# FTDI___USB.net
KiCad netlist of a schematic drawn in Altium Designer
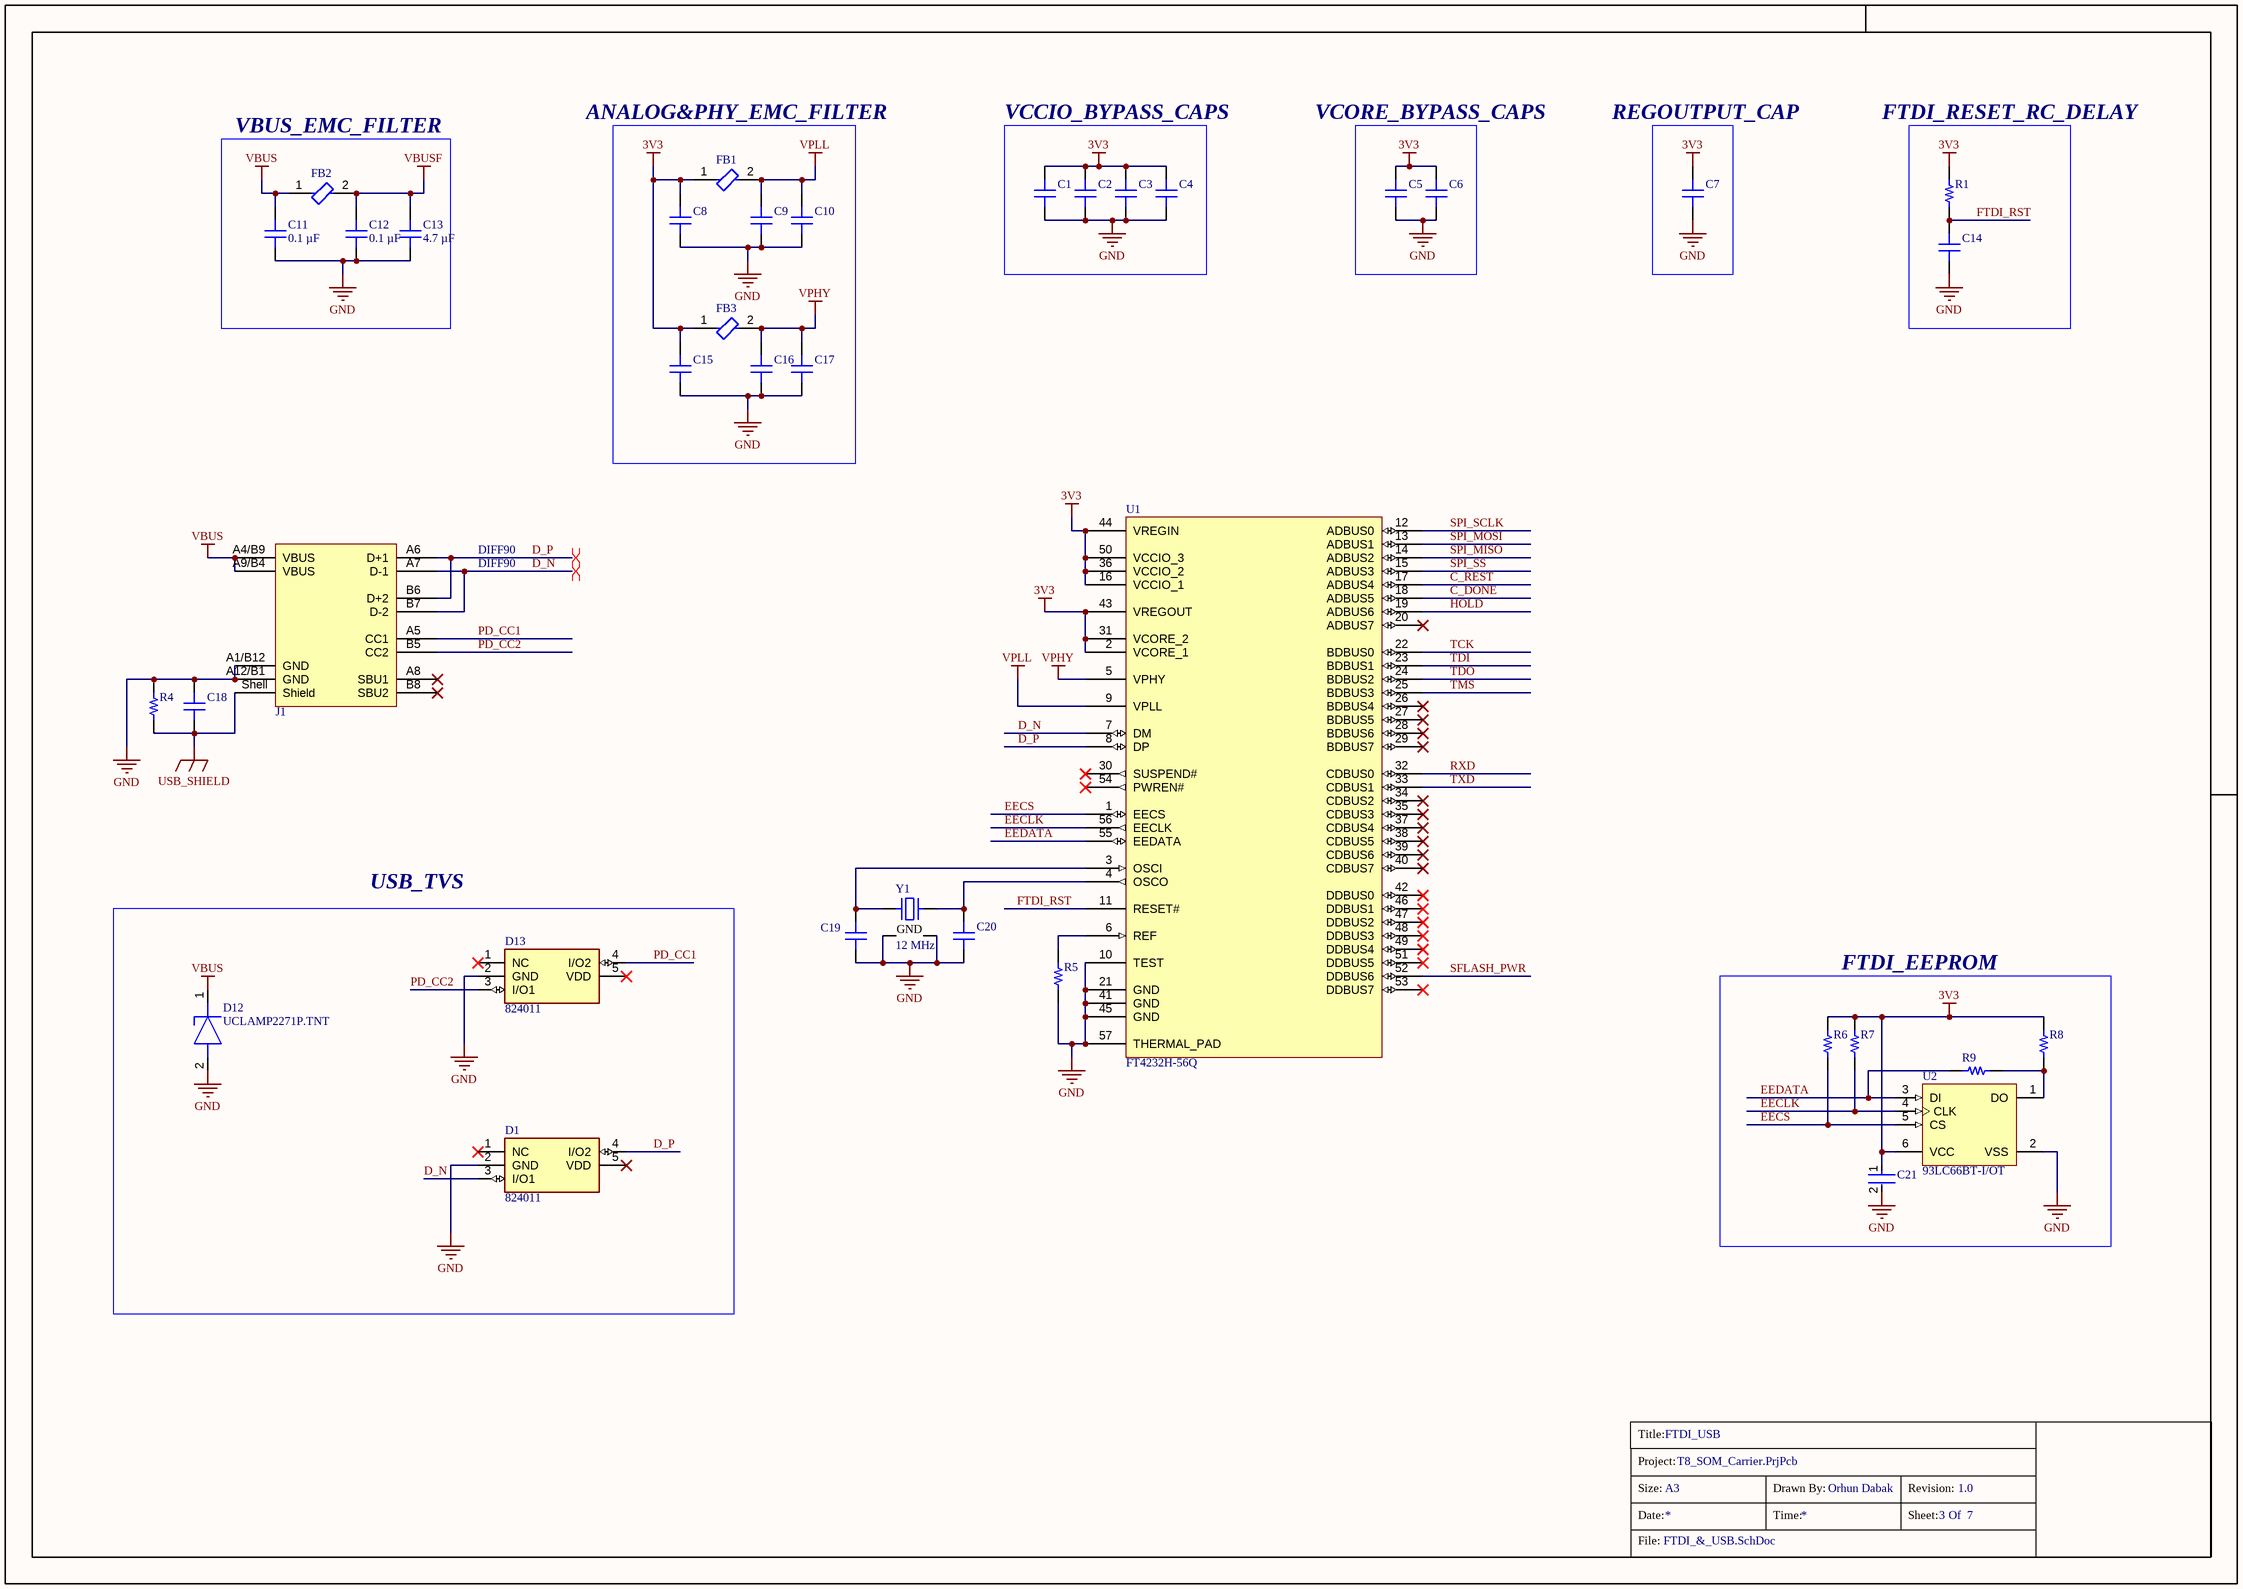
[diagram p0: FTDI_&_USB.SchDoc]

(export (version "E")
  (design (tool "Eeschema 10.0.6"))
  (components
    (comp (ref "C1")
      (value "0.1 µF")
      (footprint "CAP 0402_1005")
      (description "CAP CER 0.1UF 10V X7R 0402")
      (fields (field (name "PART NUMBER") "CC0402KRX7R6BB104") (field (name "MANUFACTURER") "Yageo"))
      (libsource (lib "Celestial Altium Library - altium_library") (part "Capacitor"))
    )
    (comp (ref "C2")
      (value "0.1 µF")
      (footprint "CAP 0402_1005")
      (description "CAP CER 0.1UF 10V X7R 0402")
      (fields (field (name "PART NUMBER") "CC0402KRX7R6BB104") (field (name "MANUFACTURER") "Yageo"))
      (libsource (lib "Celestial Altium Library - altium_library") (part "Capacitor"))
    )
    (comp (ref "C3")
      (value "0.1 µF")
      (footprint "CAP 0402_1005")
      (description "CAP CER 0.1UF 10V X7R 0402")
      (fields (field (name "PART NUMBER") "CC0402KRX7R6BB104") (field (name "MANUFACTURER") "Yageo"))
      (libsource (lib "Celestial Altium Library - altium_library") (part "Capacitor"))
    )
    (comp (ref "C4")
      (value "0.1 µF")
      (footprint "CAP 0402_1005")
      (description "CAP CER 0.1UF 10V X7R 0402")
      (fields (field (name "PART NUMBER") "CC0402KRX7R6BB104") (field (name "MANUFACTURER") "Yageo"))
      (libsource (lib "Celestial Altium Library - altium_library") (part "Capacitor"))
    )
    (comp (ref "C5")
      (value "0.1 µF")
      (footprint "CAP 0402_1005")
      (description "CAP CER 0.1UF 10V X7R 0402")
      (fields (field (name "PART NUMBER") "CC0402KRX7R6BB104") (field (name "MANUFACTURER") "Yageo"))
      (libsource (lib "Celestial Altium Library - altium_library") (part "Capacitor"))
    )
    (comp (ref "C6")
      (value "0.1 µF")
      (footprint "CAP 0402_1005")
      (description "CAP CER 0.1UF 10V X7R 0402")
      (fields (field (name "PART NUMBER") "CC0402KRX7R6BB104") (field (name "MANUFACTURER") "Yageo"))
      (libsource (lib "Celestial Altium Library - altium_library") (part "Capacitor"))
    )
    (comp (ref "C7")
      (value "4.7 µF")
      (footprint "CAP 0402_1005")
      (description "CAP CER 4.7UF 10V X5R 0402")
      (fields
        (field (name "PART NUMBER") "CL05A475MP5NRNC")
        (field (name "MANUFACTURER") "Samsung Electro-Mechanics")
      )
      (libsource (lib "Celestial Altium Library - altium_library") (part "Capacitor"))
    )
    (comp (ref "C8")
      (value "0.1 µF")
      (footprint "CAP 0402_1005")
      (description "CAP CER 0.1UF 10V X7R 0402")
      (fields (field (name "PART NUMBER") "CC0402KRX7R6BB104") (field (name "MANUFACTURER") "Yageo"))
      (libsource (lib "Celestial Altium Library - altium_library") (part "Capacitor"))
    )
    (comp (ref "C9")
      (value "0.1 µF")
      (footprint "CAP 0402_1005")
      (description "CAP CER 0.1UF 10V X7R 0402")
      (fields (field (name "PART NUMBER") "CC0402KRX7R6BB104") (field (name "MANUFACTURER") "Yageo"))
      (libsource (lib "Celestial Altium Library - altium_library") (part "Capacitor"))
    )
    (comp (ref "C10")
      (value "4.7 µF")
      (footprint "CAP 0402_1005")
      (description "CAP CER 4.7UF 10V X5R 0402")
      (fields
        (field (name "PART NUMBER") "CL05A475MP5NRNC")
        (field (name "MANUFACTURER") "Samsung Electro-Mechanics")
      )
      (libsource (lib "Celestial Altium Library - altium_library") (part "Capacitor"))
    )
    (comp (ref "C11")
      (value "0.1 µF")
      (footprint "CAP 0603_1608")
      (description "CAP CER 0.1UF 25V X7R 0603")
      (fields (field (name "PART NUMBER") "C0603X104M3RAC7867") (field (name "MANUFACTURER") "KEMET"))
      (libsource (lib "Celestial Altium Library - altium_library") (part "Capacitor"))
    )
    (comp (ref "C12")
      (value "0.1 µF")
      (footprint "CAP 0603_1608")
      (description "CAP CER 0.1UF 25V X7R 0603")
      (fields (field (name "PART NUMBER") "C0603X104M3RAC7867") (field (name "MANUFACTURER") "KEMET"))
      (libsource (lib "Celestial Altium Library - altium_library") (part "Capacitor"))
    )
    (comp (ref "C13")
      (value "4.7 µF")
      (footprint "CAP 1206_3216 - 0.8MM")
      (description "CAP CER 4.7UF 50V X7R 1206")
      (fields
        (field (name "PART NUMBER") "CL31B475KBHVPNE")
        (field (name "MANUFACTURER") "Samsung Electro-Mechanics")
      )
      (libsource (lib "Celestial Altium Library - altium_library") (part "Capacitor"))
    )
    (comp (ref "C14")
      (value "0.1 µF")
      (footprint "CAP 0402_1005")
      (description "CAP CER 0.1UF 10V X7R 0402")
      (fields (field (name "PART NUMBER") "CC0402KRX7R6BB104") (field (name "MANUFACTURER") "Yageo"))
      (libsource (lib "Celestial Altium Library - altium_library") (part "Capacitor"))
    )
    (comp (ref "C15")
      (value "0.1 µF")
      (footprint "CAP 0402_1005")
      (description "CAP CER 0.1UF 10V X7R 0402")
      (fields (field (name "PART NUMBER") "CC0402KRX7R6BB104") (field (name "MANUFACTURER") "Yageo"))
      (libsource (lib "Celestial Altium Library - altium_library") (part "Capacitor"))
    )
    (comp (ref "C16")
      (value "0.1 µF")
      (footprint "CAP 0402_1005")
      (description "CAP CER 0.1UF 10V X7R 0402")
      (fields (field (name "PART NUMBER") "CC0402KRX7R6BB104") (field (name "MANUFACTURER") "Yageo"))
      (libsource (lib "Celestial Altium Library - altium_library") (part "Capacitor"))
    )
    (comp (ref "C17")
      (value "4.7 µF")
      (footprint "CAP 0402_1005")
      (description "CAP CER 4.7UF 10V X5R 0402")
      (fields
        (field (name "PART NUMBER") "CL05A475MP5NRNC")
        (field (name "MANUFACTURER") "Samsung Electro-Mechanics")
      )
      (libsource (lib "Celestial Altium Library - altium_library") (part "Capacitor"))
    )
    (comp (ref "C18")
      (value "10000 pF")
      (footprint "CAP 0402_1005")
      (description "CAP CER 10000PF 100V X7R 0402")
      (fields (field (name "PART NUMBER") "CC0402KRX7R0BB103") (field (name "MANUFACTURER") "Yageo"))
      (libsource (lib "Celestial Altium Library - altium_library") (part "Capacitor"))
    )
    (comp (ref "C19")
      (value "18 pF")
      (footprint "CAP 0201_0603")
      (description "CAP CER 18PF 50V C0G/NP0 0201")
      (fields
        (field (name "PART NUMBER") "GRM0335C1H180JA01D")
        (field (name "MANUFACTURER") "Murata Electronics")
      )
      (libsource (lib "Celestial Altium Library - altium_library") (part "Capacitor"))
    )
    (comp (ref "C20")
      (value "18 pF")
      (footprint "CAP 0201_0603")
      (description "CAP CER 18PF 50V C0G/NP0 0201")
      (fields
        (field (name "PART NUMBER") "GRM0335C1H180JA01D")
        (field (name "MANUFACTURER") "Murata Electronics")
      )
      (libsource (lib "Celestial Altium Library - altium_library") (part "Capacitor"))
    )
    (comp (ref "C21")
      (value "EMK105B7104KV-F")
      (footprint "FP-0402-L_1_0_0_05-W_0_5-MFG")
      (description "None")
      (fields (field (name "TOLERANCE") "10%"))
      (libsource (lib "Altium Content Vault") (part "b4654b650e69147ec39a6b967a45e02"))
    )
    (comp (ref "D1")
      (value "824011")
      (footprint "SamacSys:SOT95P280X145-5N")
      (description "Diode")
      (fields (field (name "MOUSER PART NUMBER") "710-824011"))
      (libsource (lib "*") (part "824011"))
    )
    (comp (ref "D12")
      (value "UCLAMP2271P.TNT")
      (footprint "SamacSys:UCLAMP2271PTNT")
      (description "Diode ESD (Uni-directional)")
      (fields (field (name "MOUSER PART NUMBER") "947-UCLAMP2271P.TNT"))
      (libsource (lib "SamacSys") (part "UCLAMP2271P.TNT"))
    )
    (comp (ref "D13")
      (value "824011")
      (footprint "SamacSys:SOT95P280X145-5N")
      (description "Diode")
      (fields (field (name "MOUSER PART NUMBER") "710-824011"))
      (libsource (lib "*") (part "824011"))
    )
    (comp (ref "FB1")
      (value "BLM15AX601SN1D")
      (footprint "FP-BLM15-0_05-IPC_B")
      (description "Chip Ferrite Bead, 0402, 600Ω @ 100MHz, 0.34Ω, 25%, 500mA")
      (fields (field (name "TOLERANCE") "25%"))
      (libsource (lib "Altium Content Vault") (part "5f30dd21d616792df468990f7003faa"))
    )
    (comp (ref "FB2")
      (value "BLM18PG330SN1D")
      (footprint "FP-BLM18-0_15-t0_8-d1_2-MFG")
      (description "Chip Ferrite Bead, 0603, 33Ω @ 100MHz, 0.025Ω, 25%, 3A")
      (fields (field (name "TOLERANCE") "25%"))
      (libsource (lib "Altium Content Vault") (part "5f30dd21d616792df468990f7003faa"))
    )
    (comp (ref "FB3")
      (value "BLM15AX601SN1D")
      (footprint "FP-BLM15-0_05-IPC_B")
      (description "Chip Ferrite Bead, 0402, 600Ω @ 100MHz, 0.34Ω, 25%, 500mA")
      (fields (field (name "TOLERANCE") "25%"))
      (libsource (lib "Altium Content Vault") (part "5f30dd21d616792df468990f7003faa"))
    )
    (comp (ref "J1")
      (value "629722000214")
      (footprint "629722000214")
      (description "WR-USB 2.0 Type C, Receptacle, Horizontal, SMT")
      (fields (field (name "MANUFACTURER") "Wurth Elektronik"))
      (libsource (lib "Altium_WR-USB (rev22b)") (part "629722000214"))
    )
    (comp (ref "R1")
      (value "1 kOhms")
      (footprint "RES 0201_0603")
      (description "RES 1K OHM 1% 1/20W 0201")
      (fields (field (name "PART NUMBER") "RC0201FR-071KL") (field (name "MANUFACTURER") "Yageo"))
      (libsource (lib "Celestial Altium Library - altium_library") (part "Resistor"))
    )
    (comp (ref "R4")
      (value "1 MOhms")
      (footprint "RES 0402_1005")
      (description "RES SMD 1M OHM 1% 1/16W 0402")
      (fields (field (name "PART NUMBER") "AC0402FR-071ML") (field (name "MANUFACTURER") "Yageo"))
      (libsource (lib "Celestial Altium Library - altium_library") (part "Resistor"))
    )
    (comp (ref "R5")
      (value "12 kOhms")
      (footprint "RES 0201_0603")
      (description "RES 12K OHM 1% 1/20W 0201")
      (fields (field (name "PART NUMBER") "RC0201FR-0712KL") (field (name "MANUFACTURER") "Yageo"))
      (libsource (lib "Celestial Altium Library - altium_library") (part "Resistor"))
    )
    (comp (ref "R6")
      (value "10 kOhms")
      (footprint "RES 0201_0603")
      (description "RES 10K OHM 1% 1/20W 0201")
      (fields (field (name "PART NUMBER") "RC0201FR-0710KL") (field (name "MANUFACTURER") "Yageo"))
      (libsource (lib "Celestial Altium Library - altium_library") (part "Resistor"))
    )
    (comp (ref "R7")
      (value "10 kOhms")
      (footprint "RES 0201_0603")
      (description "RES 10K OHM 1% 1/20W 0201")
      (fields (field (name "PART NUMBER") "RC0201FR-0710KL") (field (name "MANUFACTURER") "Yageo"))
      (libsource (lib "Celestial Altium Library - altium_library") (part "Resistor"))
    )
    (comp (ref "R8")
      (value "10 kOhms")
      (footprint "RES 0201_0603")
      (description "RES 10K OHM 1% 1/20W 0201")
      (fields (field (name "PART NUMBER") "RC0201FR-0710KL") (field (name "MANUFACTURER") "Yageo"))
      (libsource (lib "Celestial Altium Library - altium_library") (part "Resistor"))
    )
    (comp (ref "R9")
      (value "2.2 kOhms")
      (footprint "RES 0201_0603")
      (description "RES 2.2K OHM 5% 1/20W 0201")
      (fields (field (name "PART NUMBER") "RC0201JR-072K2L") (field (name "MANUFACTURER") "Yageo"))
      (libsource (lib "Celestial Altium Library - altium_library") (part "Resistor"))
    )
    (comp (ref "U1")
      (value "FT4232H-56Q")
      (footprint "QFN50P800X800X100-57N-D")
      (description "USB Bridge, USB to UART,FIFO USB 2.0 FIFO Interface 56-VQFN (8x8)")
      (fields (field (name "MANUFACTURER") "FTDI, Future Technology Devices International Ltd"))
      (libsource (lib "T8_devkit_PCB") (part "FT4232H-56Q"))
    )
    (comp (ref "U2")
      (value "93LC66BT-I/OT")
      (footprint "SOT-23-OT6_N")
      (description "Microwire Serial EEPROM Family, 2.5Vto 5.5V' 2 MHz, -40°Cto 125°C, SOT-23-6, RoHS")
      (libsource (lib "Kocaeli University") (part "MEM-SEEPROM-93AA46B-OT-6"))
    )
    (comp (ref "Y1")
      (value "12 MHz")
      (footprint "NDK NX3225GA")
      (description "CRYSTAL 12.0000MHZ 8PF SMD")
      (fields
        (field (name "PART NUMBER") "NX3225GA-12MHZ-STD-CRG-2")
        (field (name "MANUFACTURER") "NDK America, Inc.")
      )
      (libsource (lib "Celestial Altium Library - altium_library") (part "NDK Crystal NX3225GA"))
    )
  )
  (nets
    (net (code "1") (name "/C_DONE") (class "Default")
      (node (ref "U1") (pin "18") (pinfunction "ADBUS5_18") (pintype "bidirectional"))
    )
    (net (code "2") (name "/C_REST") (class "Default")
      (node (ref "U1") (pin "17") (pinfunction "ADBUS4_17") (pintype "bidirectional"))
    )
    (net (code "3") (name "/D_N") (class "Default")
      (node (ref "D1") (pin "3") (pinfunction "I/O1_3") (pintype "bidirectional"))
      (node (ref "J1") (pin "A7") (pinfunction "D-1_A7") (pintype "passive"))
      (node (ref "J1") (pin "B7") (pinfunction "D-2_B7") (pintype "passive"))
      (node (ref "U1") (pin "7") (pinfunction "DM_7") (pintype "bidirectional"))
    )
    (net (code "4") (name "/D_P") (class "Default")
      (node (ref "D1") (pin "4") (pinfunction "I/O2_4") (pintype "bidirectional"))
      (node (ref "J1") (pin "A6") (pinfunction "D+1_A6") (pintype "passive"))
      (node (ref "J1") (pin "B6") (pinfunction "D+2_B6") (pintype "passive"))
      (node (ref "U1") (pin "8") (pinfunction "DP_8") (pintype "bidirectional"))
    )
    (net (code "5") (name "/EECLK") (class "Default")
      (node (ref "R7") (pin "1") (pinfunction "1_1") (pintype "passive"))
      (node (ref "U1") (pin "56") (pinfunction "EECLK_56") (pintype "output"))
      (node (ref "U2") (pin "4") (pinfunction "CLK_4") (pintype "input"))
    )
    (net (code "6") (name "/EECS") (class "Default")
      (node (ref "R6") (pin "1") (pinfunction "1_1") (pintype "passive"))
      (node (ref "U1") (pin "1") (pinfunction "EECS_1") (pintype "bidirectional"))
      (node (ref "U2") (pin "5") (pinfunction "CS_5") (pintype "input"))
    )
    (net (code "7") (name "/EEDATA") (class "Default")
      (node (ref "R9") (pin "1") (pinfunction "1_1") (pintype "passive"))
      (node (ref "U1") (pin "55") (pinfunction "EEDATA_55") (pintype "bidirectional"))
      (node (ref "U2") (pin "3") (pinfunction "DI_3") (pintype "input"))
    )
    (net (code "8") (name "/FTDI_RST") (class "Default")
      (node (ref "C14") (pin "2") (pinfunction "2_2") (pintype "passive"))
      (node (ref "R1") (pin "1") (pinfunction "1_1") (pintype "passive"))
      (node (ref "U1") (pin "11") (pinfunction "RESET#_11") (pintype "passive"))
    )
    (net (code "9") (name "/HOLD") (class "Default")
      (node (ref "U1") (pin "19") (pinfunction "ADBUS6_19") (pintype "bidirectional"))
    )
    (net (code "10") (name "/PD_CC1") (class "Default")
      (node (ref "D13") (pin "4") (pinfunction "I/O2_4") (pintype "bidirectional"))
      (node (ref "J1") (pin "A5") (pinfunction "CC1_A5") (pintype "passive"))
    )
    (net (code "11") (name "/PD_CC2") (class "Default")
      (node (ref "D13") (pin "3") (pinfunction "I/O1_3") (pintype "bidirectional"))
      (node (ref "J1") (pin "B5") (pinfunction "CC2_B5") (pintype "passive"))
    )
    (net (code "12") (name "/RXD") (class "Default")
      (node (ref "U1") (pin "32") (pinfunction "CDBUS0_32") (pintype "bidirectional"))
    )
    (net (code "13") (name "/SFLASH_PWR") (class "Default")
      (node (ref "U1") (pin "52") (pinfunction "DDBUS6_52") (pintype "bidirectional"))
    )
    (net (code "14") (name "/SPI_MISO") (class "Default")
      (node (ref "U1") (pin "14") (pinfunction "ADBUS2_14") (pintype "bidirectional"))
    )
    (net (code "15") (name "/SPI_MOSI") (class "Default")
      (node (ref "U1") (pin "13") (pinfunction "ADBUS1_13") (pintype "bidirectional"))
    )
    (net (code "16") (name "/SPI_SCLK") (class "Default")
      (node (ref "U1") (pin "12") (pinfunction "ADBUS0_12") (pintype "bidirectional"))
    )
    (net (code "17") (name "/SPI_SS") (class "Default")
      (node (ref "U1") (pin "15") (pinfunction "ADBUS3_15") (pintype "bidirectional"))
    )
    (net (code "18") (name "/TCK") (class "Default")
      (node (ref "U1") (pin "22") (pinfunction "BDBUS0_22") (pintype "bidirectional"))
    )
    (net (code "19") (name "/TDI") (class "Default")
      (node (ref "U1") (pin "23") (pinfunction "BDBUS1_23") (pintype "bidirectional"))
    )
    (net (code "20") (name "/TDO") (class "Default")
      (node (ref "U1") (pin "24") (pinfunction "BDBUS2_24") (pintype "bidirectional"))
    )
    (net (code "21") (name "/TMS") (class "Default")
      (node (ref "U1") (pin "25") (pinfunction "BDBUS3_25") (pintype "bidirectional"))
    )
    (net (code "22") (name "/TXD") (class "Default")
      (node (ref "U1") (pin "33") (pinfunction "CDBUS1_33") (pintype "bidirectional"))
    )
    (net (code "23") (name "3V3") (class "Default")
      (node (ref "C1") (pin "2") (pinfunction "2_2") (pintype "passive"))
      (node (ref "C15") (pin "2") (pinfunction "2_2") (pintype "passive"))
      (node (ref "C2") (pin "2") (pinfunction "2_2") (pintype "passive"))
      (node (ref "C21") (pin "1") (pinfunction "1_1") (pintype "passive"))
      (node (ref "C3") (pin "2") (pinfunction "2_2") (pintype "passive"))
      (node (ref "C4") (pin "2") (pinfunction "2_2") (pintype "passive"))
      (node (ref "C5") (pin "2") (pinfunction "2_2") (pintype "passive"))
      (node (ref "C6") (pin "2") (pinfunction "2_2") (pintype "passive"))
      (node (ref "C7") (pin "2") (pinfunction "2_2") (pintype "passive"))
      (node (ref "C8") (pin "2") (pinfunction "2_2") (pintype "passive"))
      (node (ref "FB1") (pin "1") (pinfunction "1_1") (pintype "passive"))
      (node (ref "FB3") (pin "1") (pinfunction "1_1") (pintype "passive"))
      (node (ref "R1") (pin "2") (pinfunction "2_2") (pintype "passive"))
      (node (ref "R6") (pin "2") (pinfunction "2_2") (pintype "passive"))
      (node (ref "R7") (pin "2") (pinfunction "2_2") (pintype "passive"))
      (node (ref "R8") (pin "2") (pinfunction "2_2") (pintype "passive"))
      (node (ref "U1") (pin "16") (pinfunction "VCCIO_1_16") (pintype "power_in"))
      (node (ref "U1") (pin "2") (pinfunction "VCORE_1_2") (pintype "power_in"))
      (node (ref "U1") (pin "31") (pinfunction "VCORE_2_31") (pintype "power_in"))
      (node (ref "U1") (pin "36") (pinfunction "VCCIO_2_36") (pintype "power_in"))
      (node (ref "U1") (pin "43") (pinfunction "VREGOUT_43") (pintype "power_in"))
      (node (ref "U1") (pin "44") (pinfunction "VREGIN_44") (pintype "power_in"))
      (node (ref "U1") (pin "50") (pinfunction "VCCIO_3_50") (pintype "power_in"))
      (node (ref "U2") (pin "6") (pinfunction "VCC_6") (pintype "power_in"))
    )
    (net (code "24") (name "GND") (class "Default")
      (node (ref "C1") (pin "1") (pinfunction "1_1") (pintype "passive"))
      (node (ref "C10") (pin "1") (pinfunction "1_1") (pintype "passive"))
      (node (ref "C11") (pin "1") (pinfunction "1_1") (pintype "passive"))
      (node (ref "C12") (pin "1") (pinfunction "1_1") (pintype "passive"))
      (node (ref "C13") (pin "1") (pinfunction "1_1") (pintype "passive"))
      (node (ref "C14") (pin "1") (pinfunction "1_1") (pintype "passive"))
      (node (ref "C15") (pin "1") (pinfunction "1_1") (pintype "passive"))
      (node (ref "C16") (pin "1") (pinfunction "1_1") (pintype "passive"))
      (node (ref "C17") (pin "1") (pinfunction "1_1") (pintype "passive"))
      (node (ref "C18") (pin "2") (pinfunction "2_2") (pintype "passive"))
      (node (ref "C19") (pin "1") (pinfunction "1_1") (pintype "passive"))
      (node (ref "C2") (pin "1") (pinfunction "1_1") (pintype "passive"))
      (node (ref "C20") (pin "2") (pinfunction "2_2") (pintype "passive"))
      (node (ref "C21") (pin "2") (pinfunction "2_2") (pintype "passive"))
      (node (ref "C3") (pin "1") (pinfunction "1_1") (pintype "passive"))
      (node (ref "C4") (pin "1") (pinfunction "1_1") (pintype "passive"))
      (node (ref "C5") (pin "1") (pinfunction "1_1") (pintype "passive"))
      (node (ref "C6") (pin "1") (pinfunction "1_1") (pintype "passive"))
      (node (ref "C7") (pin "1") (pinfunction "1_1") (pintype "passive"))
      (node (ref "C8") (pin "1") (pinfunction "1_1") (pintype "passive"))
      (node (ref "C9") (pin "1") (pinfunction "1_1") (pintype "passive"))
      (node (ref "D1") (pin "2") (pinfunction "GND_2") (pintype "power_in"))
      (node (ref "D12") (pin "2") (pinfunction "A_2") (pintype "passive"))
      (node (ref "D13") (pin "2") (pinfunction "GND_2") (pintype "power_in"))
      (node (ref "J1") (pin "A1/B12") (pinfunction "GND_A1/B12") (pintype "passive"))
      (node (ref "J1") (pin "A12/B1") (pinfunction "GND_A12/B1") (pintype "passive"))
      (node (ref "R4") (pin "2") (pinfunction "2_2") (pintype "passive"))
      (node (ref "R5") (pin "1") (pinfunction "1_1") (pintype "passive"))
      (node (ref "U1") (pin "10") (pinfunction "TEST_10") (pintype "passive"))
      (node (ref "U1") (pin "21") (pinfunction "GND_21") (pintype "power_in"))
      (node (ref "U1") (pin "41") (pinfunction "GND_41") (pintype "power_in"))
      (node (ref "U1") (pin "45") (pinfunction "GND_45") (pintype "power_in"))
      (node (ref "U1") (pin "57") (pinfunction "THERMAL_PAD_57") (pintype "passive"))
      (node (ref "U2") (pin "2") (pinfunction "VSS_2") (pintype "power_in"))
      (node (ref "Y1") (pin "2") (pinfunction "GND_2") (pintype "passive"))
      (node (ref "Y1") (pin "4") (pinfunction "GND_4") (pintype "passive"))
    )
    (net (code "25") (name "Net-(U1-OSCI)") (class "Default")
      (node (ref "C19") (pin "2") (pinfunction "2_2") (pintype "passive"))
      (node (ref "U1") (pin "3") (pinfunction "OSCI_3") (pintype "input"))
      (node (ref "Y1") (pin "1") (pinfunction "1_1") (pintype "passive"))
    )
    (net (code "26") (name "Net-(U1-OSCO)") (class "Default")
      (node (ref "C20") (pin "1") (pinfunction "1_1") (pintype "passive"))
      (node (ref "U1") (pin "4") (pinfunction "OSCO_4") (pintype "output"))
      (node (ref "Y1") (pin "3") (pinfunction "3_3") (pintype "passive"))
    )
    (net (code "27") (name "Net-(U1-REF)") (class "Default")
      (node (ref "R5") (pin "2") (pinfunction "2_2") (pintype "passive"))
      (node (ref "U1") (pin "6") (pinfunction "REF_6") (pintype "input"))
    )
    (net (code "28") (name "Net-(U2-DO)") (class "Default")
      (node (ref "R8") (pin "1") (pinfunction "1_1") (pintype "passive"))
      (node (ref "R9") (pin "2") (pinfunction "2_2") (pintype "passive"))
      (node (ref "U2") (pin "1") (pinfunction "DO_1") (pintype "tri_state"))
    )
    (net (code "29") (name "USB_SHIELD") (class "Default")
      (node (ref "C18") (pin "1") (pinfunction "1_1") (pintype "passive"))
      (node (ref "J1") (pin "Shell") (pinfunction "Shield_Shell") (pintype "passive"))
      (node (ref "R4") (pin "1") (pinfunction "1_1") (pintype "passive"))
    )
    (net (code "30") (name "VBUS") (class "Default")
      (node (ref "C11") (pin "2") (pinfunction "2_2") (pintype "passive"))
      (node (ref "D12") (pin "1") (pinfunction "K_1") (pintype "passive"))
      (node (ref "FB2") (pin "1") (pinfunction "1_1") (pintype "passive"))
      (node (ref "J1") (pin "A4/B9") (pinfunction "VBUS_A4/B9") (pintype "passive"))
      (node (ref "J1") (pin "A9/B4") (pinfunction "VBUS_A9/B4") (pintype "passive"))
    )
    (net (code "31") (name "VBUSF") (class "Default")
      (node (ref "C12") (pin "2") (pinfunction "2_2") (pintype "passive"))
      (node (ref "C13") (pin "2") (pinfunction "2_2") (pintype "passive"))
      (node (ref "FB2") (pin "2") (pinfunction "2_2") (pintype "passive"))
    )
    (net (code "32") (name "VPHY") (class "Default")
      (node (ref "C16") (pin "2") (pinfunction "2_2") (pintype "passive"))
      (node (ref "C17") (pin "2") (pinfunction "2_2") (pintype "passive"))
      (node (ref "FB3") (pin "2") (pinfunction "2_2") (pintype "passive"))
      (node (ref "U1") (pin "5") (pinfunction "VPHY_5") (pintype "power_in"))
    )
    (net (code "33") (name "VPLL") (class "Default")
      (node (ref "C10") (pin "2") (pinfunction "2_2") (pintype "passive"))
      (node (ref "C9") (pin "2") (pinfunction "2_2") (pintype "passive"))
      (node (ref "FB1") (pin "2") (pinfunction "2_2") (pintype "passive"))
      (node (ref "U1") (pin "9") (pinfunction "VPLL_9") (pintype "power_in"))
    )
    (net (code "34") (name "unconnected-(D1-NC-Pad1)") (class "Default")
      (node (ref "D1") (pin "1") (pinfunction "NC_1") (pintype "passive+no_connect"))
    )
    (net (code "35") (name "unconnected-(D1-VDD-Pad5)") (class "Default")
      (node (ref "D1") (pin "5") (pinfunction "VDD_5") (pintype "power_in+no_connect"))
    )
    (net (code "36") (name "unconnected-(D13-NC-Pad1)") (class "Default")
      (node (ref "D13") (pin "1") (pinfunction "NC_1") (pintype "passive+no_connect"))
    )
    (net (code "37") (name "unconnected-(D13-VDD-Pad5)") (class "Default")
      (node (ref "D13") (pin "5") (pinfunction "VDD_5") (pintype "power_in+no_connect"))
    )
    (net (code "38") (name "unconnected-(J1-SBU1-PadA8)") (class "Default")
      (node (ref "J1") (pin "A8") (pinfunction "SBU1_A8") (pintype "passive+no_connect"))
    )
    (net (code "39") (name "unconnected-(J1-SBU2-PadB8)") (class "Default")
      (node (ref "J1") (pin "B8") (pinfunction "SBU2_B8") (pintype "passive+no_connect"))
    )
    (net (code "40") (name "unconnected-(U1-ADBUS7-Pad20)") (class "Default")
      (node (ref "U1") (pin "20") (pinfunction "ADBUS7_20") (pintype "bidirectional+no_connect"))
    )
    (net (code "41") (name "unconnected-(U1-BDBUS4-Pad26)") (class "Default")
      (node (ref "U1") (pin "26") (pinfunction "BDBUS4_26") (pintype "bidirectional+no_connect"))
    )
    (net (code "42") (name "unconnected-(U1-BDBUS5-Pad27)") (class "Default")
      (node (ref "U1") (pin "27") (pinfunction "BDBUS5_27") (pintype "bidirectional+no_connect"))
    )
    (net (code "43") (name "unconnected-(U1-BDBUS6-Pad28)") (class "Default")
      (node (ref "U1") (pin "28") (pinfunction "BDBUS6_28") (pintype "bidirectional+no_connect"))
    )
    (net (code "44") (name "unconnected-(U1-BDBUS7-Pad29)") (class "Default")
      (node (ref "U1") (pin "29") (pinfunction "BDBUS7_29") (pintype "bidirectional+no_connect"))
    )
    (net (code "45") (name "unconnected-(U1-CDBUS2-Pad34)") (class "Default")
      (node (ref "U1") (pin "34") (pinfunction "CDBUS2_34") (pintype "bidirectional+no_connect"))
    )
    (net (code "46") (name "unconnected-(U1-CDBUS3-Pad35)") (class "Default")
      (node (ref "U1") (pin "35") (pinfunction "CDBUS3_35") (pintype "bidirectional+no_connect"))
    )
    (net (code "47") (name "unconnected-(U1-CDBUS4-Pad37)") (class "Default")
      (node (ref "U1") (pin "37") (pinfunction "CDBUS4_37") (pintype "bidirectional+no_connect"))
    )
    (net (code "48") (name "unconnected-(U1-CDBUS5-Pad38)") (class "Default")
      (node (ref "U1") (pin "38") (pinfunction "CDBUS5_38") (pintype "bidirectional+no_connect"))
    )
    (net (code "49") (name "unconnected-(U1-CDBUS6-Pad39)") (class "Default")
      (node (ref "U1") (pin "39") (pinfunction "CDBUS6_39") (pintype "bidirectional+no_connect"))
    )
    (net (code "50") (name "unconnected-(U1-CDBUS7-Pad40)") (class "Default")
      (node (ref "U1") (pin "40") (pinfunction "CDBUS7_40") (pintype "bidirectional+no_connect"))
    )
    (net (code "51") (name "unconnected-(U1-DDBUS0-Pad42)") (class "Default")
      (node (ref "U1") (pin "42") (pinfunction "DDBUS0_42") (pintype "bidirectional+no_connect"))
    )
    (net (code "52") (name "unconnected-(U1-DDBUS1-Pad46)") (class "Default")
      (node (ref "U1") (pin "46") (pinfunction "DDBUS1_46") (pintype "bidirectional+no_connect"))
    )
    (net (code "53") (name "unconnected-(U1-DDBUS2-Pad47)") (class "Default")
      (node (ref "U1") (pin "47") (pinfunction "DDBUS2_47") (pintype "bidirectional+no_connect"))
    )
    (net (code "54") (name "unconnected-(U1-DDBUS3-Pad48)") (class "Default")
      (node (ref "U1") (pin "48") (pinfunction "DDBUS3_48") (pintype "bidirectional+no_connect"))
    )
    (net (code "55") (name "unconnected-(U1-DDBUS4-Pad49)") (class "Default")
      (node (ref "U1") (pin "49") (pinfunction "DDBUS4_49") (pintype "bidirectional+no_connect"))
    )
    (net (code "56") (name "unconnected-(U1-DDBUS5-Pad51)") (class "Default")
      (node (ref "U1") (pin "51") (pinfunction "DDBUS5_51") (pintype "bidirectional+no_connect"))
    )
    (net (code "57") (name "unconnected-(U1-DDBUS7-Pad53)") (class "Default")
      (node (ref "U1") (pin "53") (pinfunction "DDBUS7_53") (pintype "bidirectional+no_connect"))
    )
    (net (code "58") (name "unconnected-(U1-PWREN#-Pad54)") (class "Default")
      (node (ref "U1") (pin "54") (pinfunction "PWREN#_54") (pintype "output+no_connect"))
    )
    (net (code "59") (name "unconnected-(U1-SUSPEND#-Pad30)") (class "Default")
      (node (ref "U1") (pin "30") (pinfunction "SUSPEND#_30") (pintype "output+no_connect"))
    )
  )
)
